# M628X.net
KiCad netlist of a schematic drawn in EAGLE
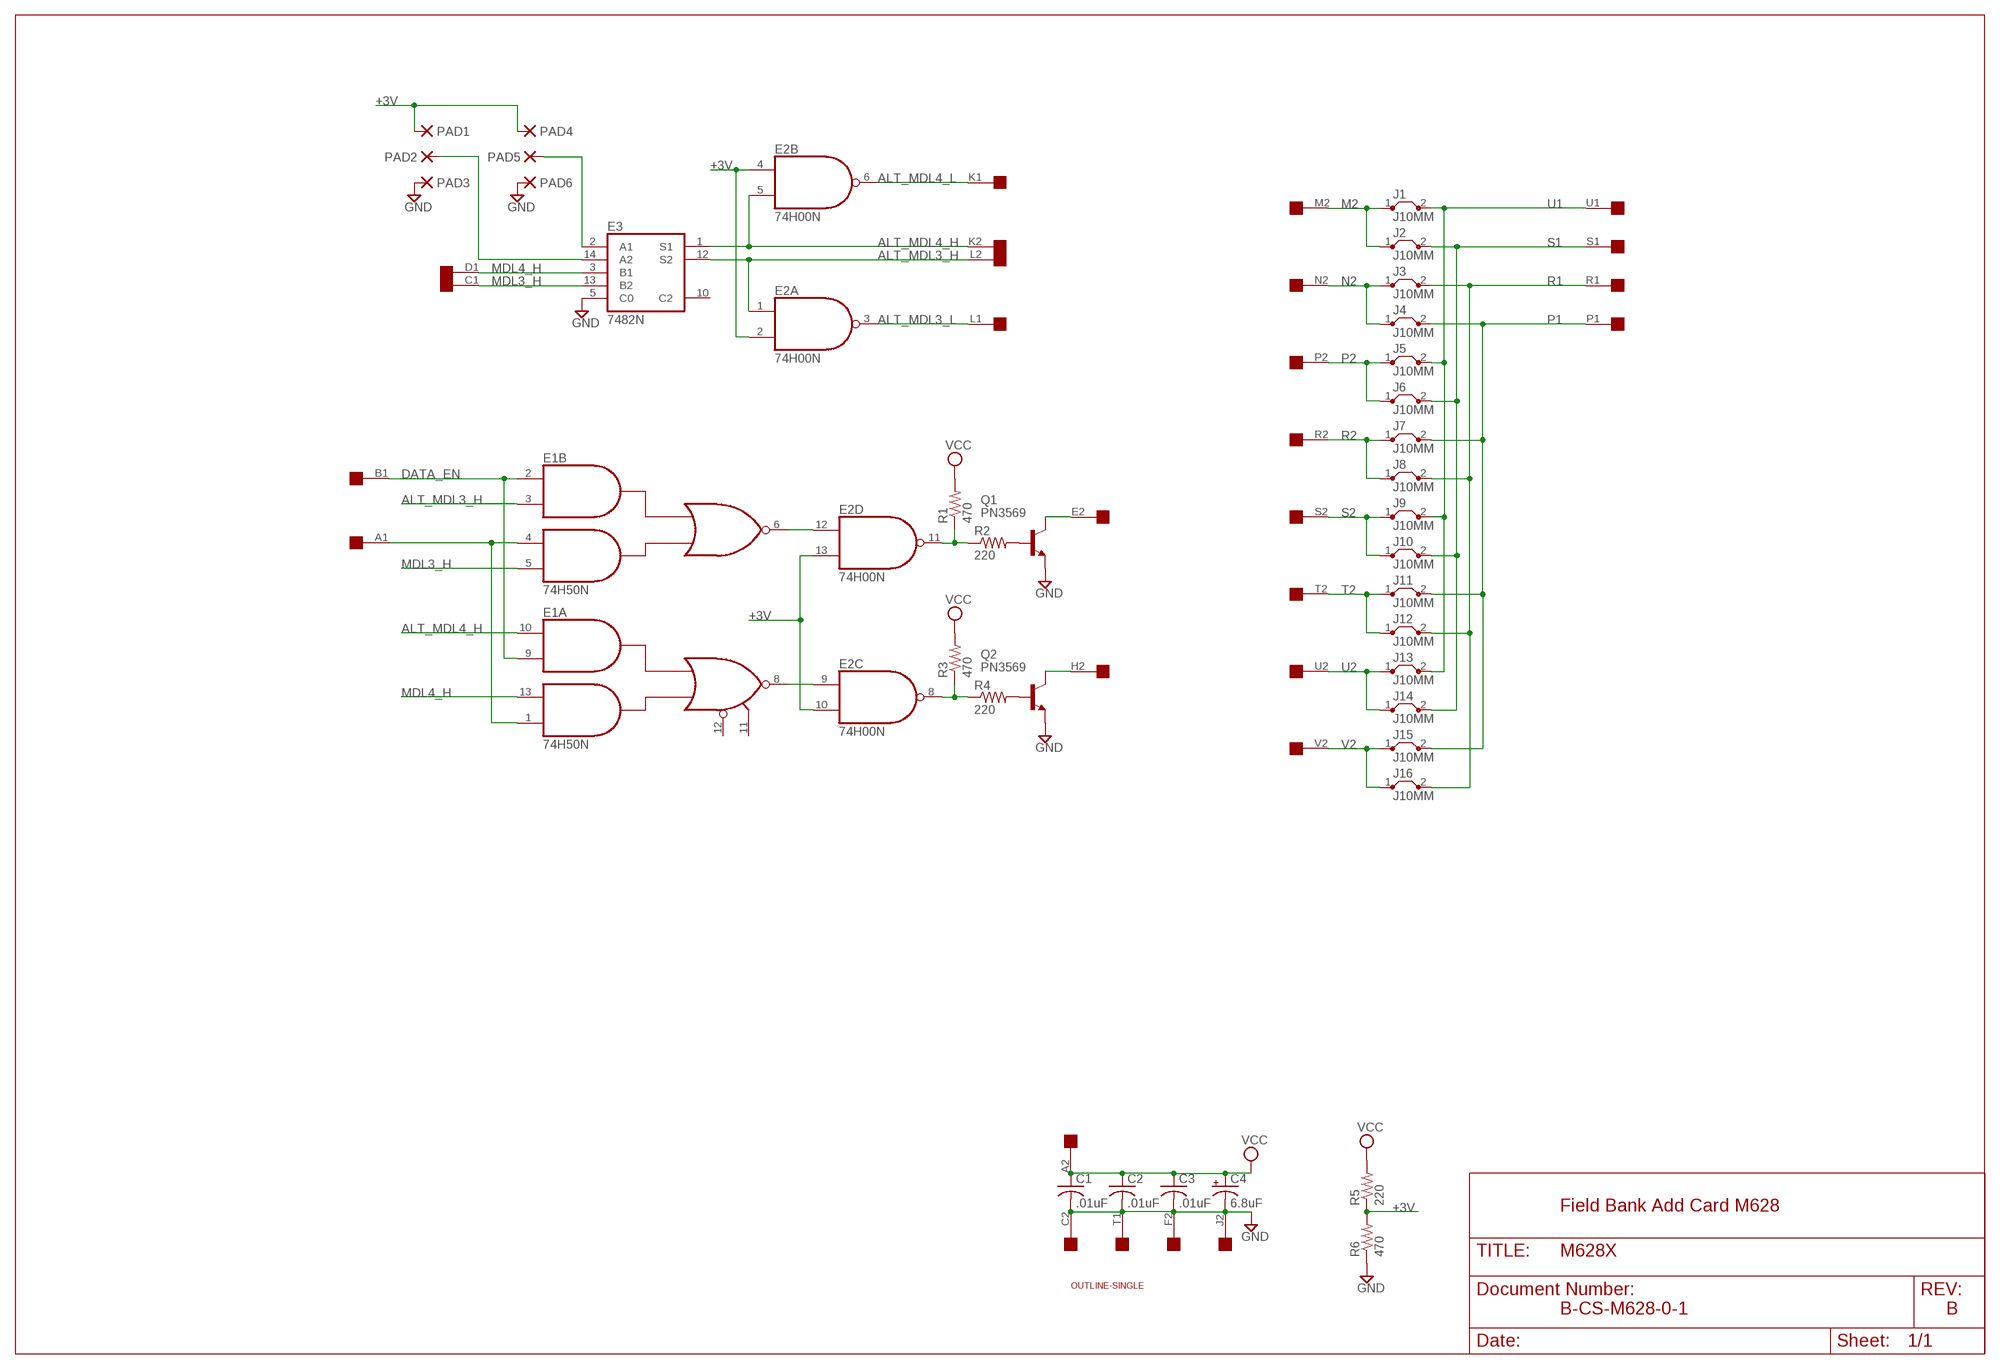
[diagram p0: schematic, sheet 1]

(export (version "E")
  (design (tool "Eeschema 10.0.6"))
  (components
    (comp (ref "C1")
      (value ".01uF")
      (footprint "eagle-import:C050-025X075")
      (libsource (lib "eagle-import") (part "C-US050-025X075"))
    )
    (comp (ref "C2")
      (value ".01uF")
      (footprint "eagle-import:C050-025X075")
      (libsource (lib "eagle-import") (part "C-US050-025X075"))
    )
    (comp (ref "C3")
      (value ".01uF")
      (footprint "eagle-import:C050-025X075")
      (libsource (lib "eagle-import") (part "C-US050-025X075"))
    )
    (comp (ref "C4")
      (value "6.8uF")
      (footprint "eagle-import:E12-8")
      (libsource (lib "eagle-import") (part "CPOL-USE20-8AXIAL"))
    )
    (comp (ref "E1")
      (value "74H50N")
      (footprint "eagle-import:DIL14")
      (libsource (lib "eagle-import") (part "7450N"))
    )
    (comp (ref "E2")
      (value "74H00N")
      (footprint "eagle-import:DIL14")
      (libsource (lib "eagle-import") (part "7400N"))
    )
    (comp (ref "E3")
      (value "7482N")
      (footprint "eagle-import:DIL14")
      (libsource (lib "eagle-import") (part "7482N"))
    )
    (comp (ref "J1")
      (value "J10MM")
      (footprint "eagle-import:10")
      (libsource (lib "eagle-import") (part "J10MM"))
    )
    (comp (ref "J2")
      (value "J10MM")
      (footprint "eagle-import:10")
      (libsource (lib "eagle-import") (part "J10MM"))
    )
    (comp (ref "J3")
      (value "J10MM")
      (footprint "eagle-import:10")
      (libsource (lib "eagle-import") (part "J10MM"))
    )
    (comp (ref "J4")
      (value "J10MM")
      (footprint "eagle-import:10")
      (libsource (lib "eagle-import") (part "J10MM"))
    )
    (comp (ref "J5")
      (value "J10MM")
      (footprint "eagle-import:10")
      (libsource (lib "eagle-import") (part "J10MM"))
    )
    (comp (ref "J6")
      (value "J10MM")
      (footprint "eagle-import:10")
      (libsource (lib "eagle-import") (part "J10MM"))
    )
    (comp (ref "J7")
      (value "J10MM")
      (footprint "eagle-import:10")
      (libsource (lib "eagle-import") (part "J10MM"))
    )
    (comp (ref "J8")
      (value "J10MM")
      (footprint "eagle-import:10")
      (libsource (lib "eagle-import") (part "J10MM"))
    )
    (comp (ref "J9")
      (value "J10MM")
      (footprint "eagle-import:10")
      (libsource (lib "eagle-import") (part "J10MM"))
    )
    (comp (ref "J10")
      (value "J10MM")
      (footprint "eagle-import:10")
      (libsource (lib "eagle-import") (part "J10MM"))
    )
    (comp (ref "J11")
      (value "J10MM")
      (footprint "eagle-import:10")
      (libsource (lib "eagle-import") (part "J10MM"))
    )
    (comp (ref "J12")
      (value "J10MM")
      (footprint "eagle-import:10")
      (libsource (lib "eagle-import") (part "J10MM"))
    )
    (comp (ref "J13")
      (value "J10MM")
      (footprint "eagle-import:10")
      (libsource (lib "eagle-import") (part "J10MM"))
    )
    (comp (ref "J14")
      (value "J10MM")
      (footprint "eagle-import:10")
      (libsource (lib "eagle-import") (part "J10MM"))
    )
    (comp (ref "J15")
      (value "J10MM")
      (footprint "eagle-import:10")
      (libsource (lib "eagle-import") (part "J10MM"))
    )
    (comp (ref "J16")
      (value "J10MM")
      (footprint "eagle-import:10")
      (libsource (lib "eagle-import") (part "J10MM"))
    )
    (comp (ref "PAD1")
      (value "PAD-0420")
      (footprint "eagle-import:0420")
      (libsource (lib "eagle-import") (part "PAD-0420"))
    )
    (comp (ref "PAD2")
      (value "PAD-0420")
      (footprint "eagle-import:0420")
      (libsource (lib "eagle-import") (part "PAD-0420"))
    )
    (comp (ref "PAD3")
      (value "PAD-0420")
      (footprint "eagle-import:0420")
      (libsource (lib "eagle-import") (part "PAD-0420"))
    )
    (comp (ref "PAD4")
      (value "PAD-0420")
      (footprint "eagle-import:0420")
      (libsource (lib "eagle-import") (part "PAD-0420"))
    )
    (comp (ref "PAD5")
      (value "PAD-0420")
      (footprint "eagle-import:0420")
      (libsource (lib "eagle-import") (part "PAD-0420"))
    )
    (comp (ref "PAD6")
      (value "PAD-0420")
      (footprint "eagle-import:0420")
      (libsource (lib "eagle-import") (part "PAD-0420"))
    )
    (comp (ref "Q1")
      (value "PN3569")
      (footprint "eagle-import:TO5")
      (libsource (lib "eagle-import") (part "2N2102"))
    )
    (comp (ref "Q2")
      (value "PN3569")
      (footprint "eagle-import:TO5")
      (libsource (lib "eagle-import") (part "2N2102"))
    )
    (comp (ref "R1")
      (value "470")
      (footprint "eagle-import:0207_10")
      (libsource (lib "eagle-import") (part "R-US_0207/10"))
    )
    (comp (ref "R2")
      (value "220")
      (footprint "eagle-import:0207_10")
      (libsource (lib "eagle-import") (part "R-US_0207/10"))
    )
    (comp (ref "R3")
      (value "470")
      (footprint "eagle-import:0207_10")
      (libsource (lib "eagle-import") (part "R-US_0207/10"))
    )
    (comp (ref "R4")
      (value "220")
      (footprint "eagle-import:0207_10")
      (libsource (lib "eagle-import") (part "R-US_0207/10"))
    )
    (comp (ref "R5")
      (value "220")
      (footprint "eagle-import:0207_10")
      (libsource (lib "eagle-import") (part "R-US_0207/10"))
    )
    (comp (ref "R6")
      (value "470")
      (footprint "eagle-import:0207_10")
      (libsource (lib "eagle-import") (part "R-US_0207/10"))
    )
    (comp (ref "U$1")
      (value "OUTLINE-SINGLE")
      (footprint "eagle-import:SINGLE")
      (libsource (lib "eagle-import") (part "OUTLINE-SINGLE"))
    )
    (comp (ref "U$2")
      (value "SINGLE")
      (footprint "eagle-import:EDGE-CON2")
      (libsource (lib "eagle-import") (part "SINGLE"))
    )
  )
  (nets
    (net (code "1") (name "/+3V") (class "Default")
      (node (ref "E2") (pin "10") (pinfunction "I1_10") (pintype "input"))
      (node (ref "E2") (pin "13") (pinfunction "I1_13") (pintype "input"))
      (node (ref "E2") (pin "2") (pinfunction "I1_2") (pintype "input"))
      (node (ref "E2") (pin "4") (pinfunction "I0_4") (pintype "input"))
      (node (ref "PAD1") (pin "P$1") (pinfunction "P_P$1") (pintype "passive"))
      (node (ref "PAD4") (pin "P$1") (pinfunction "P_P$1") (pintype "passive"))
      (node (ref "R5") (pin "1") (pinfunction "1_1") (pintype "passive"))
      (node (ref "R6") (pin "2") (pinfunction "2_2") (pintype "passive"))
    )
    (net (code "2") (name "/ALT_MDL3_H") (class "Default")
      (node (ref "E1") (pin "3") (pinfunction "I2_3") (pintype "input"))
      (node (ref "E2") (pin "1") (pinfunction "I0_1") (pintype "input"))
      (node (ref "E3") (pin "12") (pinfunction "S2_12") (pintype "output"))
      (node (ref "U$2") (pin "L2") (pinfunction "1_L2") (pintype "bidirectional"))
    )
    (net (code "3") (name "/ALT_MDL3_L") (class "Default")
      (node (ref "E2") (pin "3") (pinfunction "O_3") (pintype "output"))
      (node (ref "U$2") (pin "L1") (pinfunction "1_L1") (pintype "bidirectional"))
    )
    (net (code "4") (name "/ALT_MDL4_H") (class "Default")
      (node (ref "E1") (pin "10") (pinfunction "I1_10") (pintype "input"))
      (node (ref "E2") (pin "5") (pinfunction "I1_5") (pintype "input"))
      (node (ref "E3") (pin "1") (pinfunction "S1_1") (pintype "output"))
      (node (ref "U$2") (pin "K2") (pinfunction "1_K2") (pintype "bidirectional"))
    )
    (net (code "5") (name "/ALT_MDL4_L") (class "Default")
      (node (ref "E2") (pin "6") (pinfunction "O_6") (pintype "output"))
      (node (ref "U$2") (pin "K1") (pinfunction "1_K1") (pintype "bidirectional"))
    )
    (net (code "6") (name "/DATA_EN") (class "Default")
      (node (ref "E1") (pin "2") (pinfunction "I1_2") (pintype "input"))
      (node (ref "E1") (pin "9") (pinfunction "I2_9") (pintype "input"))
      (node (ref "U$2") (pin "B1") (pinfunction "1_B1") (pintype "bidirectional"))
    )
    (net (code "7") (name "/M2") (class "Default")
      (node (ref "J1") (pin "1") (pinfunction "1_1") (pintype "passive"))
      (node (ref "J2") (pin "1") (pinfunction "1_1") (pintype "passive"))
      (node (ref "U$2") (pin "M2") (pinfunction "1_M2") (pintype "bidirectional"))
    )
    (net (code "8") (name "/MDL3_H") (class "Default")
      (node (ref "E1") (pin "5") (pinfunction "I4_5") (pintype "input"))
      (node (ref "E3") (pin "13") (pinfunction "B2_13") (pintype "input"))
      (node (ref "U$2") (pin "C1") (pinfunction "1_C1") (pintype "bidirectional"))
    )
    (net (code "9") (name "/MDL4_H") (class "Default")
      (node (ref "E1") (pin "13") (pinfunction "I3_13") (pintype "input"))
      (node (ref "E3") (pin "3") (pinfunction "B1_3") (pintype "input"))
      (node (ref "U$2") (pin "D1") (pinfunction "1_D1") (pintype "bidirectional"))
    )
    (net (code "10") (name "/N2") (class "Default")
      (node (ref "J3") (pin "1") (pinfunction "1_1") (pintype "passive"))
      (node (ref "J4") (pin "1") (pinfunction "1_1") (pintype "passive"))
      (node (ref "U$2") (pin "N2") (pinfunction "1_N2") (pintype "bidirectional"))
    )
    (net (code "11") (name "/P1") (class "Default")
      (node (ref "J11") (pin "2") (pinfunction "2_2") (pintype "passive"))
      (node (ref "J15") (pin "2") (pinfunction "2_2") (pintype "passive"))
      (node (ref "J4") (pin "2") (pinfunction "2_2") (pintype "passive"))
      (node (ref "J7") (pin "2") (pinfunction "2_2") (pintype "passive"))
      (node (ref "U$2") (pin "P1") (pinfunction "1_P1") (pintype "bidirectional"))
    )
    (net (code "12") (name "/P2") (class "Default")
      (node (ref "J5") (pin "1") (pinfunction "1_1") (pintype "passive"))
      (node (ref "J6") (pin "1") (pinfunction "1_1") (pintype "passive"))
      (node (ref "U$2") (pin "P2") (pinfunction "1_P2") (pintype "bidirectional"))
    )
    (net (code "13") (name "/R1") (class "Default")
      (node (ref "J12") (pin "2") (pinfunction "2_2") (pintype "passive"))
      (node (ref "J16") (pin "2") (pinfunction "2_2") (pintype "passive"))
      (node (ref "J3") (pin "2") (pinfunction "2_2") (pintype "passive"))
      (node (ref "J8") (pin "2") (pinfunction "2_2") (pintype "passive"))
      (node (ref "U$2") (pin "R1") (pinfunction "1_R1") (pintype "bidirectional"))
    )
    (net (code "14") (name "/R2") (class "Default")
      (node (ref "J7") (pin "1") (pinfunction "1_1") (pintype "passive"))
      (node (ref "J8") (pin "1") (pinfunction "1_1") (pintype "passive"))
      (node (ref "U$2") (pin "R2") (pinfunction "1_R2") (pintype "bidirectional"))
    )
    (net (code "15") (name "/S1") (class "Default")
      (node (ref "J10") (pin "2") (pinfunction "2_2") (pintype "passive"))
      (node (ref "J14") (pin "2") (pinfunction "2_2") (pintype "passive"))
      (node (ref "J2") (pin "2") (pinfunction "2_2") (pintype "passive"))
      (node (ref "J6") (pin "2") (pinfunction "2_2") (pintype "passive"))
      (node (ref "U$2") (pin "S1") (pinfunction "1_S1") (pintype "bidirectional"))
    )
    (net (code "16") (name "/S2") (class "Default")
      (node (ref "J10") (pin "1") (pinfunction "1_1") (pintype "passive"))
      (node (ref "J9") (pin "1") (pinfunction "1_1") (pintype "passive"))
      (node (ref "U$2") (pin "S2") (pinfunction "1_S2") (pintype "bidirectional"))
    )
    (net (code "17") (name "/T2") (class "Default")
      (node (ref "J11") (pin "1") (pinfunction "1_1") (pintype "passive"))
      (node (ref "J12") (pin "1") (pinfunction "1_1") (pintype "passive"))
      (node (ref "U$2") (pin "T2") (pinfunction "1_T2") (pintype "bidirectional"))
    )
    (net (code "18") (name "/U1") (class "Default")
      (node (ref "J1") (pin "2") (pinfunction "2_2") (pintype "passive"))
      (node (ref "J13") (pin "2") (pinfunction "2_2") (pintype "passive"))
      (node (ref "J5") (pin "2") (pinfunction "2_2") (pintype "passive"))
      (node (ref "J9") (pin "2") (pinfunction "2_2") (pintype "passive"))
      (node (ref "U$2") (pin "U1") (pinfunction "1_U1") (pintype "bidirectional"))
    )
    (net (code "19") (name "/U2") (class "Default")
      (node (ref "J13") (pin "1") (pinfunction "1_1") (pintype "passive"))
      (node (ref "J14") (pin "1") (pinfunction "1_1") (pintype "passive"))
      (node (ref "U$2") (pin "U2") (pinfunction "1_U2") (pintype "bidirectional"))
    )
    (net (code "20") (name "/V2") (class "Default")
      (node (ref "J15") (pin "1") (pinfunction "1_1") (pintype "passive"))
      (node (ref "J16") (pin "1") (pinfunction "1_1") (pintype "passive"))
      (node (ref "U$2") (pin "V2") (pinfunction "1_V2") (pintype "bidirectional"))
    )
    (net (code "21") (name "GND") (class "Default")
      (node (ref "C1") (pin "2") (pinfunction "2_2") (pintype "passive"))
      (node (ref "C2") (pin "2") (pinfunction "2_2") (pintype "passive"))
      (node (ref "C3") (pin "2") (pinfunction "2_2") (pintype "passive"))
      (node (ref "C4") (pin "-") (pinfunction "-_-") (pintype "passive"))
      (node (ref "E3") (pin "5") (pinfunction "C0_5") (pintype "input"))
      (node (ref "PAD3") (pin "P$1") (pinfunction "P_P$1") (pintype "passive"))
      (node (ref "PAD6") (pin "P$1") (pinfunction "P_P$1") (pintype "passive"))
      (node (ref "Q1") (pin "1") (pinfunction "E_1") (pintype "passive"))
      (node (ref "Q2") (pin "1") (pinfunction "E_1") (pintype "passive"))
      (node (ref "R6") (pin "1") (pinfunction "1_1") (pintype "passive"))
      (node (ref "U$2") (pin "C2") (pinfunction "1_C2") (pintype "bidirectional"))
      (node (ref "U$2") (pin "F2") (pinfunction "1_F2") (pintype "bidirectional"))
      (node (ref "U$2") (pin "J2") (pinfunction "1_J2") (pintype "bidirectional"))
      (node (ref "U$2") (pin "T1") (pinfunction "1_T1") (pintype "bidirectional"))
    )
    (net (code "22") (name "Net-(E1A-I4)") (class "Default")
      (node (ref "E1") (pin "1") (pinfunction "I4_1") (pintype "input"))
      (node (ref "E1") (pin "4") (pinfunction "I3_4") (pintype "input"))
      (node (ref "U$2") (pin "A1") (pinfunction "1_A1") (pintype "bidirectional"))
    )
    (net (code "23") (name "Net-(E1A-O)") (class "Default")
      (node (ref "E1") (pin "8") (pinfunction "O_8") (pintype "output"))
      (node (ref "E2") (pin "9") (pinfunction "I0_9") (pintype "input"))
    )
    (net (code "24") (name "Net-(E1B-O)") (class "Default")
      (node (ref "E1") (pin "6") (pinfunction "O_6") (pintype "output"))
      (node (ref "E2") (pin "12") (pinfunction "I0_12") (pintype "input"))
    )
    (net (code "25") (name "Net-(E2C-O)") (class "Default")
      (node (ref "E2") (pin "8") (pinfunction "O_8") (pintype "output"))
      (node (ref "R3") (pin "1") (pinfunction "1_1") (pintype "passive"))
      (node (ref "R4") (pin "1") (pinfunction "1_1") (pintype "passive"))
    )
    (net (code "26") (name "Net-(E2D-O)") (class "Default")
      (node (ref "E2") (pin "11") (pinfunction "O_11") (pintype "output"))
      (node (ref "R1") (pin "1") (pinfunction "1_1") (pintype "passive"))
      (node (ref "R2") (pin "1") (pinfunction "1_1") (pintype "passive"))
    )
    (net (code "27") (name "Net-(E3E-A1)") (class "Default")
      (node (ref "E3") (pin "2") (pinfunction "A1_2") (pintype "input"))
      (node (ref "PAD5") (pin "P$1") (pinfunction "P_P$1") (pintype "passive"))
    )
    (net (code "28") (name "Net-(E3E-A2)") (class "Default")
      (node (ref "E3") (pin "14") (pinfunction "A2_14") (pintype "input"))
      (node (ref "PAD2") (pin "P$1") (pinfunction "P_P$1") (pintype "passive"))
    )
    (net (code "29") (name "Net-(Q1-B)") (class "Default")
      (node (ref "Q1") (pin "2") (pinfunction "B_2") (pintype "passive"))
      (node (ref "R2") (pin "2") (pinfunction "2_2") (pintype "passive"))
    )
    (net (code "30") (name "Net-(Q1-C)") (class "Default")
      (node (ref "Q1") (pin "3") (pinfunction "C_3") (pintype "passive"))
      (node (ref "U$2") (pin "E2") (pinfunction "1_E2") (pintype "bidirectional"))
    )
    (net (code "31") (name "Net-(Q2-B)") (class "Default")
      (node (ref "Q2") (pin "2") (pinfunction "B_2") (pintype "passive"))
      (node (ref "R4") (pin "2") (pinfunction "2_2") (pintype "passive"))
    )
    (net (code "32") (name "Net-(Q2-C)") (class "Default")
      (node (ref "Q2") (pin "3") (pinfunction "C_3") (pintype "passive"))
      (node (ref "U$2") (pin "H2") (pinfunction "1_H2") (pintype "bidirectional"))
    )
    (net (code "33") (name "VCC") (class "Default")
      (node (ref "C1") (pin "1") (pinfunction "1_1") (pintype "passive"))
      (node (ref "C2") (pin "1") (pinfunction "1_1") (pintype "passive"))
      (node (ref "C3") (pin "1") (pinfunction "1_1") (pintype "passive"))
      (node (ref "C4") (pin "+") (pinfunction "+_+") (pintype "passive"))
      (node (ref "R1") (pin "2") (pinfunction "2_2") (pintype "passive"))
      (node (ref "R3") (pin "2") (pinfunction "2_2") (pintype "passive"))
      (node (ref "R5") (pin "2") (pinfunction "2_2") (pintype "passive"))
      (node (ref "U$2") (pin "A2") (pinfunction "1_A2") (pintype "bidirectional"))
    )
    (net (code "34") (name "unconnected-(E1A-I5-Pad12)") (class "Default")
      (node (ref "E1") (pin "12") (pinfunction "I5_12") (pintype "passive"))
    )
    (net (code "35") (name "unconnected-(E1A-I6-Pad11)") (class "Default")
      (node (ref "E1") (pin "11") (pinfunction "I6_11") (pintype "passive"))
    )
    (net (code "36") (name "unconnected-(E3E-C2-Pad10)") (class "Default")
      (node (ref "E3") (pin "10") (pinfunction "C2_10") (pintype "output"))
    )
  )
)
